# flex_probe.net
KiCad netlist of a schematic drawn in EAGLE
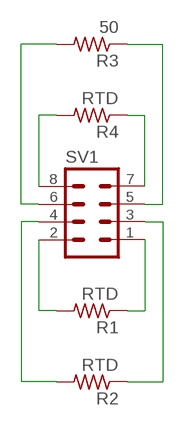
[diagram p0: schematic, sheet 1]

(export (version "E")
  (design (tool "Eeschema 10.0.6"))
  (components
    (comp (ref "R1")
      (value "RTD")
      (footprint "eagle-import:R0603")
      (libsource (lib "eagle-import") (part "R-US_R0603"))
    )
    (comp (ref "R2")
      (value "RTD")
      (footprint "eagle-import:R0603")
      (libsource (lib "eagle-import") (part "R-US_R0603"))
    )
    (comp (ref "R3")
      (value "50")
      (footprint "eagle-import:R0603")
      (libsource (lib "eagle-import") (part "R-US_R0603"))
    )
    (comp (ref "R4")
      (value "RTD")
      (footprint "eagle-import:R0603")
      (libsource (lib "eagle-import") (part "R-US_R0603"))
    )
    (comp (ref "SV1")
      (value "MA04-2")
      (footprint "eagle-import:MA04-2")
      (libsource (lib "eagle-import") (part "MA04-2"))
    )
  )
  (nets
    (net (code "1") (name "Net-(R1-Pad1)") (class "Default")
      (node (ref "R1") (pin "1") (pinfunction "1_1") (pintype "passive"))
      (node (ref "SV1") (pin "1") (pinfunction "1_1") (pintype "passive"))
    )
    (net (code "2") (name "Net-(R1-Pad2)") (class "Default")
      (node (ref "R1") (pin "2") (pinfunction "2_2") (pintype "passive"))
      (node (ref "SV1") (pin "2") (pinfunction "2_2") (pintype "passive"))
    )
    (net (code "3") (name "Net-(R2-Pad1)") (class "Default")
      (node (ref "R2") (pin "1") (pinfunction "1_1") (pintype "passive"))
      (node (ref "SV1") (pin "3") (pinfunction "3_3") (pintype "passive"))
    )
    (net (code "4") (name "Net-(R2-Pad2)") (class "Default")
      (node (ref "R2") (pin "2") (pinfunction "2_2") (pintype "passive"))
      (node (ref "SV1") (pin "4") (pinfunction "4_4") (pintype "passive"))
    )
    (net (code "5") (name "Net-(R3-Pad1)") (class "Default")
      (node (ref "R3") (pin "1") (pinfunction "1_1") (pintype "passive"))
      (node (ref "SV1") (pin "5") (pinfunction "5_5") (pintype "passive"))
    )
    (net (code "6") (name "Net-(R3-Pad2)") (class "Default")
      (node (ref "R3") (pin "2") (pinfunction "2_2") (pintype "passive"))
      (node (ref "SV1") (pin "6") (pinfunction "6_6") (pintype "passive"))
    )
    (net (code "7") (name "Net-(R4-Pad1)") (class "Default")
      (node (ref "R4") (pin "1") (pinfunction "1_1") (pintype "passive"))
      (node (ref "SV1") (pin "7") (pinfunction "7_7") (pintype "passive"))
    )
    (net (code "8") (name "Net-(R4-Pad2)") (class "Default")
      (node (ref "R4") (pin "2") (pinfunction "2_2") (pintype "passive"))
      (node (ref "SV1") (pin "8") (pinfunction "8_8") (pintype "passive"))
    )
  )
)
